# SCH_NFC_CARD_2024-10-16.net
KiCad netlist of a schematic drawn in EasyEDA
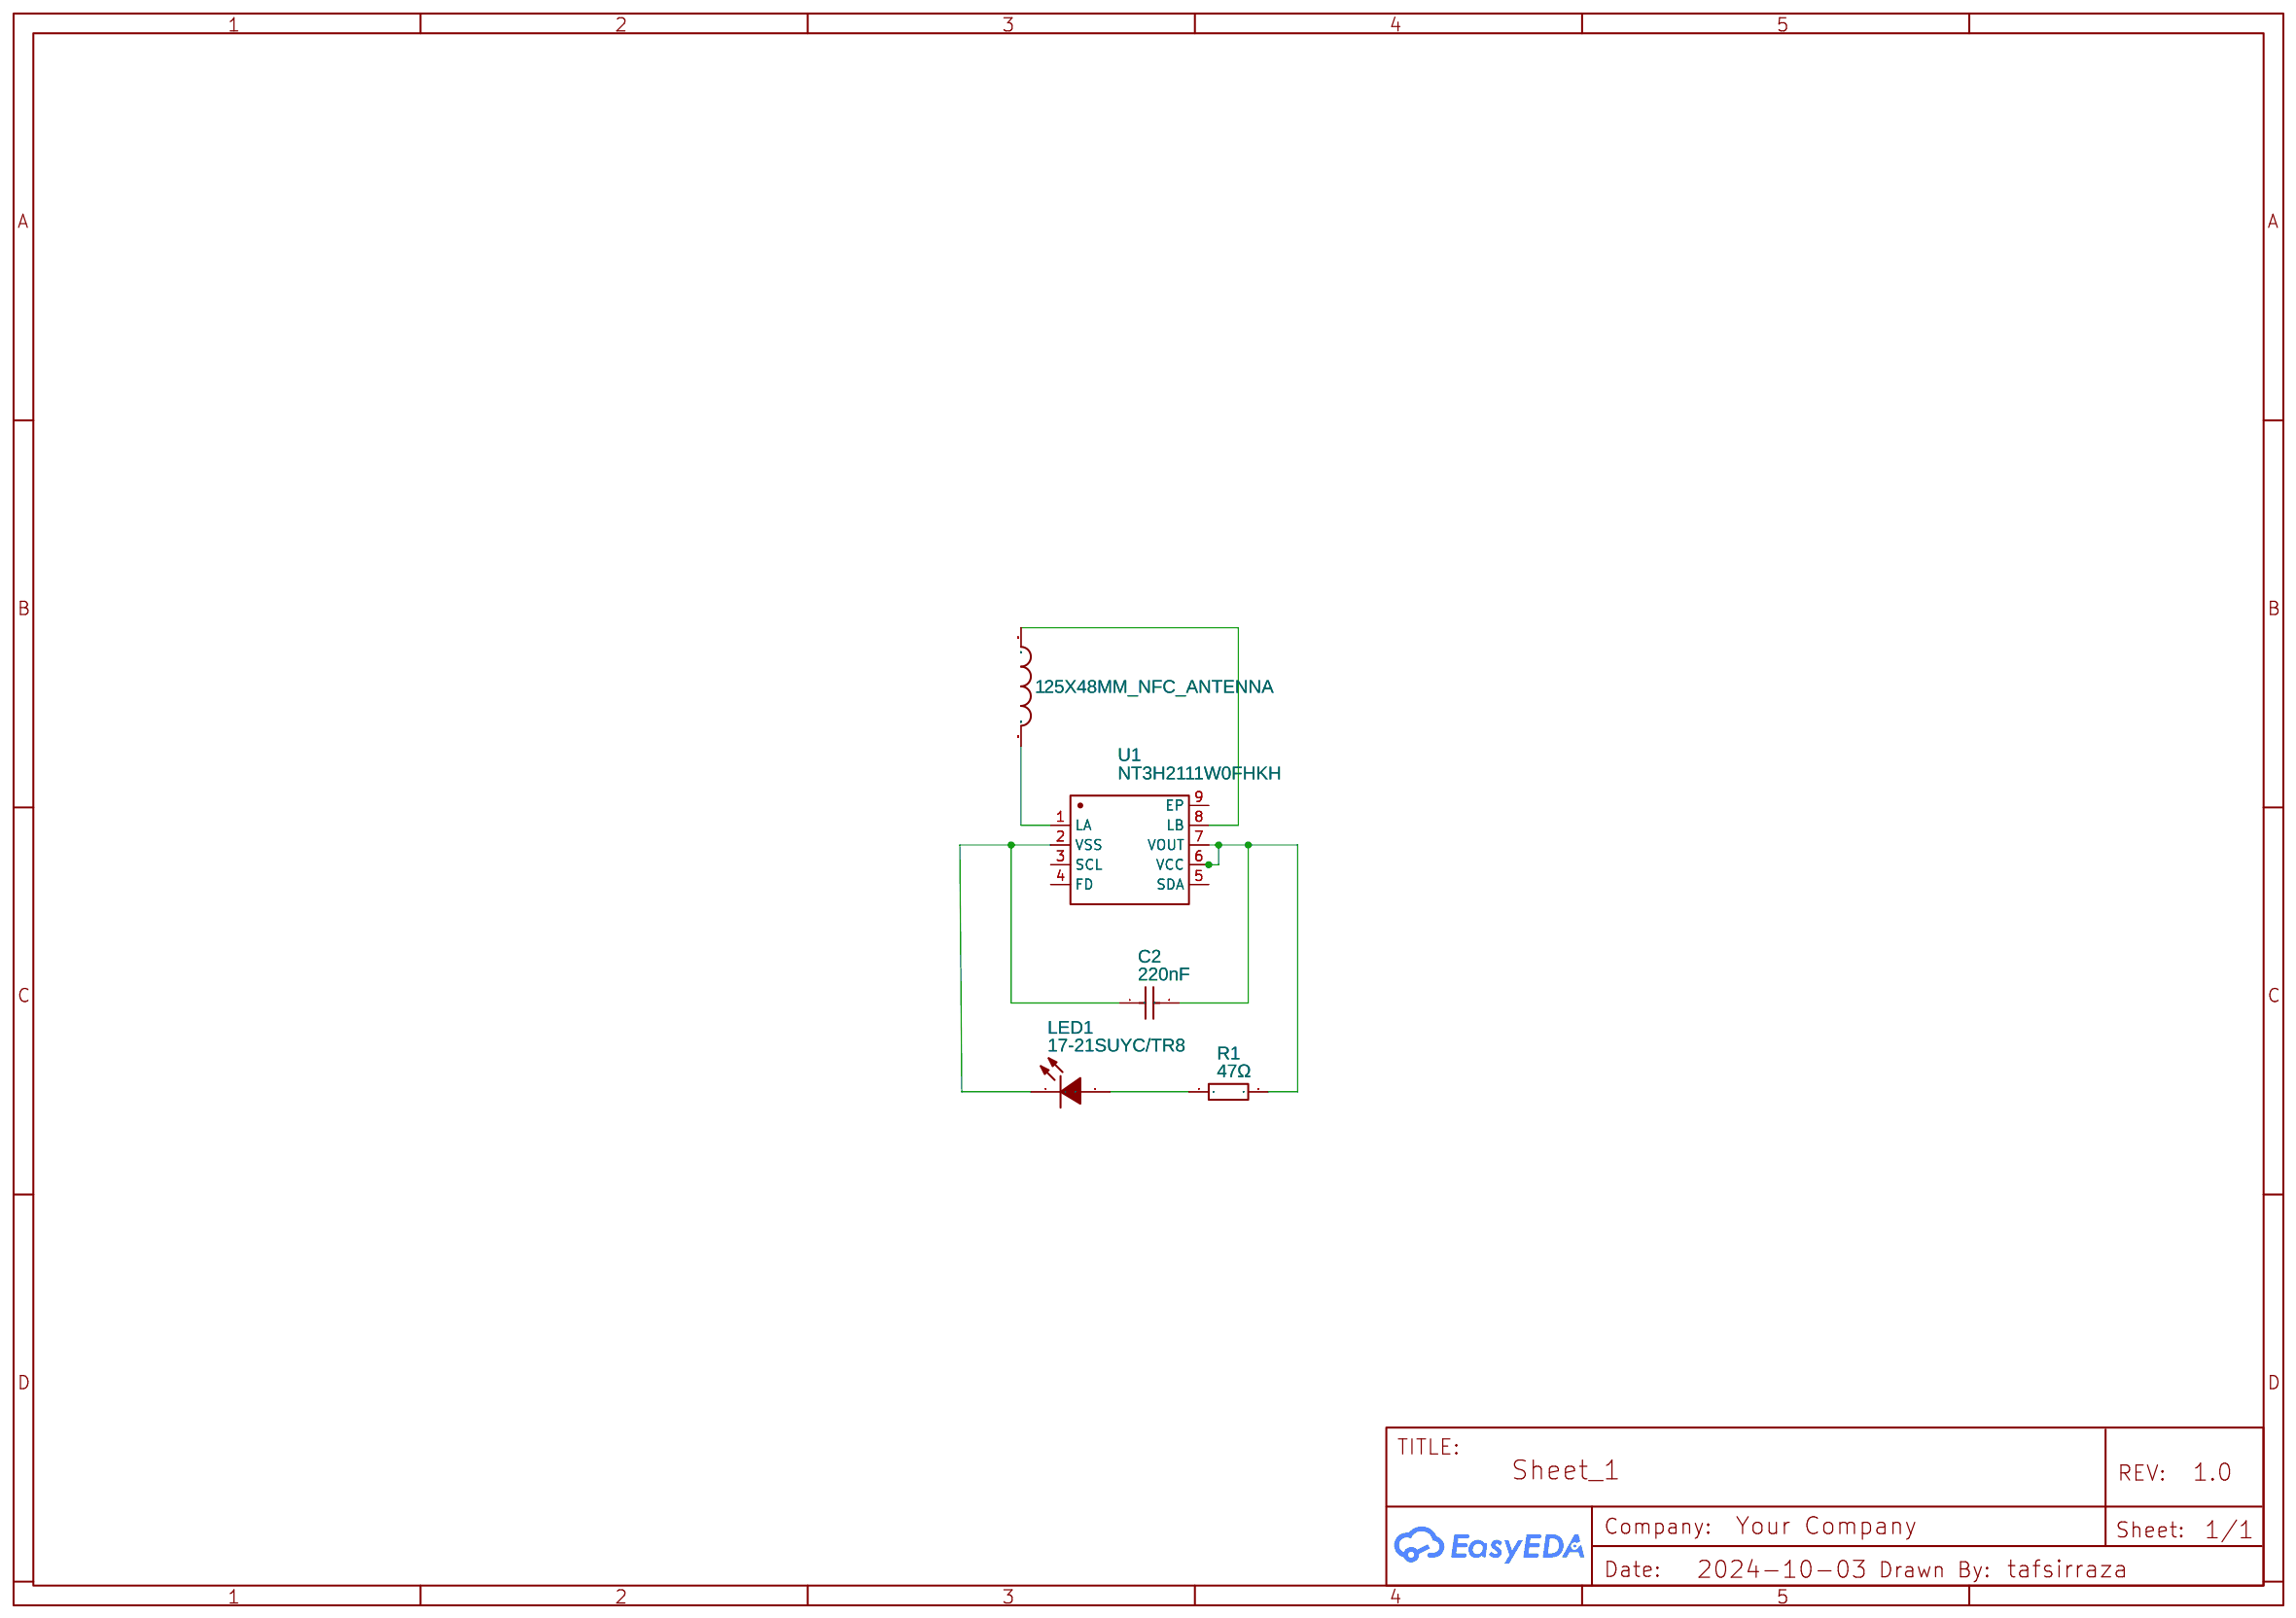
[diagram p0: schematic sheet]

(export (version "E")
  (design (tool "Eeschema 10.0.6"))
  (components
    (comp (ref "1") (value "25X48MM_NFC_ANTENNA") (libsource (lib "") (part "25X48MM_NFC_ANTENNA")))
    (comp (ref "C2")
      (value "220nF")
      (fields
        (field (name "Manufacturer Part") "CL10B224KA8NNNC")
        (field (name "Manufacturer") "SAMSUNG(三星)")
      )
      (libsource (lib "") (part "CL10B224KA8NNNC"))
    )
    (comp (ref "LED1")
      (value "17-21SUYC/TR8")
      (fields (field (name "Manufacturer Part") "KT-0805黄灯") (field (name "Manufacturer") "KENTO"))
      (libsource (lib "") (part "17-21SUYC/TR8"))
    )
    (comp (ref "R1")
      (value "47Ω")
      (fields
        (field (name "Manufacturer Part") "0603WAF470JT5E")
        (field (name "Manufacturer") "UNI-ROYAL(厚声)")
      )
      (libsource (lib "") (part "0603WAF470JT5E"))
    )
    (comp (ref "U1")
      (value "NT3H2111W0FHKH")
      (fields (field (name "Manufacturer") "NXP(恩智浦)"))
      (libsource (lib "") (part "NT3H2111W0FHKH"))
    )
  )
  (nets
    (net (code "1") (name "Net-(LED1-+)") (class "Default")
      (node (ref "LED1") (pin "1") (pinfunction "+_1") (pintype "unspecified"))
      (node (ref "R1") (pin "1") (pinfunction "1_1") (pintype "input"))
    )
    (net (code "2") (name "Net-(LED1--)") (class "Default")
      (node (ref "C2") (pin "1") (pinfunction "1_1") (pintype "input"))
      (node (ref "LED1") (pin "2") (pinfunction "-_2") (pintype "unspecified"))
      (node (ref "U1") (pin "2") (pinfunction "VSS_2") (pintype "unspecified"))
    )
    (net (code "3") (name "Net-(U1-LA)") (class "Default")
      (node (ref "1") (pin "P$2") (pinfunction "P$2_P$2") (pintype "unspecified"))
      (node (ref "U1") (pin "1") (pinfunction "LA_1") (pintype "unspecified"))
    )
    (net (code "4") (name "Net-(U1-LB)") (class "Default")
      (node (ref "1") (pin "P$1") (pinfunction "P$1_P$1") (pintype "unspecified"))
      (node (ref "U1") (pin "8") (pinfunction "LB_8") (pintype "unspecified"))
    )
    (net (code "5") (name "Net-(U1-VCC)") (class "Default")
      (node (ref "C2") (pin "2") (pinfunction "2_2") (pintype "input"))
      (node (ref "R1") (pin "2") (pinfunction "2_2") (pintype "input"))
      (node (ref "U1") (pin "6") (pinfunction "VCC_6") (pintype "unspecified"))
      (node (ref "U1") (pin "7") (pinfunction "VOUT_7") (pintype "unspecified"))
    )
    (net (code "6") (name "unconnected-(U1-EP-Pad9)") (class "Default")
      (node (ref "U1") (pin "9") (pinfunction "EP_9") (pintype "unspecified"))
    )
    (net (code "7") (name "unconnected-(U1-FD-Pad4)") (class "Default")
      (node (ref "U1") (pin "4") (pinfunction "FD_4") (pintype "unspecified"))
    )
    (net (code "8") (name "unconnected-(U1-SCL-Pad3)") (class "Default")
      (node (ref "U1") (pin "3") (pinfunction "SCL_3") (pintype "unspecified"))
    )
    (net (code "9") (name "unconnected-(U1-SDA-Pad5)") (class "Default")
      (node (ref "U1") (pin "5") (pinfunction "SDA_5") (pintype "unspecified"))
    )
  )
)
